# combo_-_no_usb.net
KiCad netlist of a schematic drawn in EAGLE
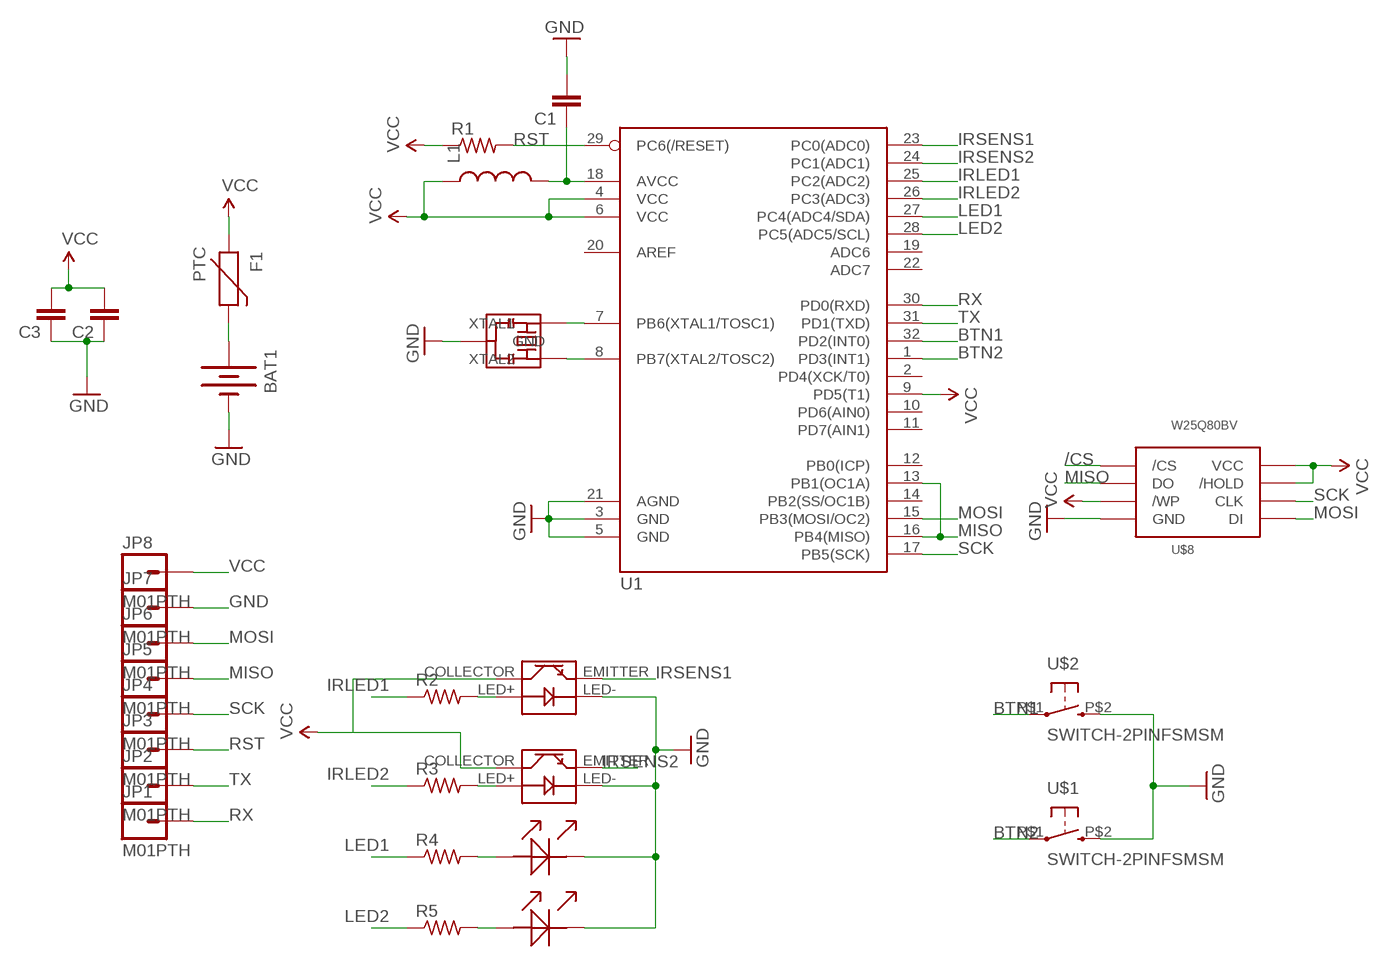
[diagram p0: schematic, sheet 1]

(export (version "E")
  (design (tool "Eeschema 10.0.6"))
  (components
    (comp (ref "BAT1")
      (value "BATTERYBA2032SM")
      (footprint "eagle-import:BA2032SM")
      (libsource (lib "eagle-import") (part "BATTERYBA2032SM"))
    )
    (comp (ref "C1")
      (value "CAP0805")
      (footprint "eagle-import:0805")
      (libsource (lib "eagle-import") (part "CAP0805"))
    )
    (comp (ref "C2")
      (value "CAP0805")
      (footprint "eagle-import:0805")
      (libsource (lib "eagle-import") (part "CAP0805"))
    )
    (comp (ref "C3")
      (value "CAP0805")
      (footprint "eagle-import:0805")
      (libsource (lib "eagle-import") (part "CAP0805"))
    )
    (comp (ref "F1")
      (value "PTC")
      (footprint "eagle-import:R0805")
      (libsource (lib "eagle-import") (part "PTC"))
    )
    (comp (ref "JP1")
      (value "M01PTH")
      (footprint "eagle-import:1X01")
      (libsource (lib "eagle-import") (part "M01PTH"))
    )
    (comp (ref "JP2")
      (value "M01PTH")
      (footprint "eagle-import:1X01")
      (libsource (lib "eagle-import") (part "M01PTH"))
    )
    (comp (ref "JP3")
      (value "M01PTH")
      (footprint "eagle-import:1X01")
      (libsource (lib "eagle-import") (part "M01PTH"))
    )
    (comp (ref "JP4")
      (value "M01PTH")
      (footprint "eagle-import:1X01")
      (libsource (lib "eagle-import") (part "M01PTH"))
    )
    (comp (ref "JP5")
      (value "M01PTH")
      (footprint "eagle-import:1X01")
      (libsource (lib "eagle-import") (part "M01PTH"))
    )
    (comp (ref "JP6")
      (value "M01PTH")
      (footprint "eagle-import:1X01")
      (libsource (lib "eagle-import") (part "M01PTH"))
    )
    (comp (ref "JP7")
      (value "M01PTH")
      (footprint "eagle-import:1X01")
      (libsource (lib "eagle-import") (part "M01PTH"))
    )
    (comp (ref "JP8")
      (value "M01PTH")
      (footprint "eagle-import:1X01")
      (libsource (lib "eagle-import") (part "M01PTH"))
    )
    (comp (ref "L1")
      (value "INDUCTOR0805")
      (footprint "eagle-import:0805")
      (libsource (lib "eagle-import") (part "INDUCTOR0805"))
    )
    (comp (ref "R1")
      (value "R-US_M0805")
      (footprint "eagle-import:M0805")
      (libsource (lib "eagle-import") (part "R-US_M0805"))
    )
    (comp (ref "R2")
      (value "R-US_M0805")
      (footprint "eagle-import:M0805")
      (libsource (lib "eagle-import") (part "R-US_M0805"))
    )
    (comp (ref "R3")
      (value "R-US_M0805")
      (footprint "eagle-import:M0805")
      (libsource (lib "eagle-import") (part "R-US_M0805"))
    )
    (comp (ref "R4")
      (value "R-US_M0805")
      (footprint "eagle-import:M0805")
      (libsource (lib "eagle-import") (part "R-US_M0805"))
    )
    (comp (ref "R5")
      (value "R-US_M0805")
      (footprint "eagle-import:M0805")
      (libsource (lib "eagle-import") (part "R-US_M0805"))
    )
    (comp (ref "U$1")
      (value "SWITCH-2PINFSMSM")
      (footprint "eagle-import:FSMSM-BUTTON")
      (libsource (lib "eagle-import") (part "SWITCH-2PINFSMSM"))
    )
    (comp (ref "U$2")
      (value "SWITCH-2PINFSMSM")
      (footprint "eagle-import:FSMSM-BUTTON")
      (libsource (lib "eagle-import") (part "SWITCH-2PINFSMSM"))
    )
    (comp (ref "U$3")
      (value "IR_SENSORQRE1113")
      (footprint "eagle-import:QRE1113")
      (libsource (lib "eagle-import") (part "IR_SENSORQRE1113"))
    )
    (comp (ref "U$4")
      (value "IR_SENSORQRE1113")
      (footprint "eagle-import:QRE1113")
      (libsource (lib "eagle-import") (part "IR_SENSORQRE1113"))
    )
    (comp (ref "U$5")
      (value "LED0603")
      (footprint "eagle-import:0603")
      (libsource (lib "eagle-import") (part "LED0603"))
    )
    (comp (ref "U$6")
      (value "LED0603")
      (footprint "eagle-import:0603")
      (libsource (lib "eagle-import") (part "LED0603"))
    )
    (comp (ref "U$7")
      (value "RESONATOR_W_CAPS")
      (footprint "eagle-import:AWSCR-CV")
      (libsource (lib "eagle-import") (part "RESONATOR_W_CAPS"))
    )
    (comp (ref "U$8")
      (value "W25Q80BVSOIC-08")
      (footprint "eagle-import:W25Q80BV-SOIC-208MIL")
      (libsource (lib "eagle-import") (part "W25Q80BVSOIC-08"))
    )
    (comp (ref "U1")
      (value "ATMEGA328_SMT")
      (footprint "eagle-import:TQFP32-08-THIN")
      (libsource (lib "eagle-import") (part "ATMEGA328_SMT"))
    )
  )
  (nets
    (net (code "1") (name "/BTN1") (class "Default")
      (node (ref "U$2") (pin "P$1") (pinfunction "1_P$1") (pintype "passive"))
      (node (ref "U1") (pin "32") (pinfunction "PD2(INT0)_32") (pintype "bidirectional"))
    )
    (net (code "2") (name "/BTN2") (class "Default")
      (node (ref "U$1") (pin "P$1") (pinfunction "1_P$1") (pintype "passive"))
      (node (ref "U1") (pin "1") (pinfunction "PD3(INT1)_1") (pintype "bidirectional"))
    )
    (net (code "3") (name "/IRLED1") (class "Default")
      (node (ref "R2") (pin "1") (pinfunction "1_1") (pintype "passive"))
      (node (ref "U1") (pin "25") (pinfunction "PC2(ADC2)_25") (pintype "bidirectional"))
    )
    (net (code "4") (name "/IRLED2") (class "Default")
      (node (ref "R3") (pin "1") (pinfunction "1_1") (pintype "passive"))
      (node (ref "U1") (pin "26") (pinfunction "PC3(ADC3)_26") (pintype "bidirectional"))
    )
    (net (code "5") (name "/IRSENS1") (class "Default")
      (node (ref "U$3") (pin "EMITTER") (pinfunction "EMITTER_EMITTER") (pintype "input"))
      (node (ref "U1") (pin "23") (pinfunction "PC0(ADC0)_23") (pintype "bidirectional"))
    )
    (net (code "6") (name "/IRSENS2") (class "Default")
      (node (ref "U$4") (pin "EMITTER") (pinfunction "EMITTER_EMITTER") (pintype "input"))
      (node (ref "U1") (pin "24") (pinfunction "PC1(ADC1)_24") (pintype "bidirectional"))
    )
    (net (code "7") (name "/LED1") (class "Default")
      (node (ref "R4") (pin "1") (pinfunction "1_1") (pintype "passive"))
      (node (ref "U1") (pin "27") (pinfunction "PC4(ADC4/SDA)_27") (pintype "bidirectional"))
    )
    (net (code "8") (name "/LED2") (class "Default")
      (node (ref "R5") (pin "1") (pinfunction "1_1") (pintype "passive"))
      (node (ref "U1") (pin "28") (pinfunction "PC5(ADC5/SCL)_28") (pintype "bidirectional"))
    )
    (net (code "9") (name "/MISO") (class "Default")
      (node (ref "JP5") (pin "1") (pinfunction "1_1") (pintype "passive"))
      (node (ref "U$8") (pin "DO") (pinfunction "DO_DO") (pintype "bidirectional"))
      (node (ref "U1") (pin "13") (pinfunction "PB1(OC1A)_13") (pintype "bidirectional"))
      (node (ref "U1") (pin "16") (pinfunction "PB4(MISO)_16") (pintype "bidirectional"))
    )
    (net (code "10") (name "/MOSI") (class "Default")
      (node (ref "JP6") (pin "1") (pinfunction "1_1") (pintype "passive"))
      (node (ref "U$8") (pin "DI") (pinfunction "DI_DI") (pintype "bidirectional"))
      (node (ref "U1") (pin "15") (pinfunction "PB3(MOSI/OC2)_15") (pintype "bidirectional"))
    )
    (net (code "11") (name "/RST") (class "Default")
      (node (ref "JP3") (pin "1") (pinfunction "1_1") (pintype "passive"))
      (node (ref "R1") (pin "2") (pinfunction "2_2") (pintype "passive"))
      (node (ref "U1") (pin "29") (pinfunction "PC6(/RESET)_29") (pintype "bidirectional"))
    )
    (net (code "12") (name "/RX") (class "Default")
      (node (ref "JP1") (pin "1") (pinfunction "1_1") (pintype "passive"))
      (node (ref "U1") (pin "30") (pinfunction "PD0(RXD)_30") (pintype "bidirectional"))
    )
    (net (code "13") (name "/SCK") (class "Default")
      (node (ref "JP4") (pin "1") (pinfunction "1_1") (pintype "passive"))
      (node (ref "U$8") (pin "CLK") (pinfunction "CLK_CLK") (pintype "input"))
      (node (ref "U1") (pin "17") (pinfunction "PB5(SCK)_17") (pintype "bidirectional"))
    )
    (net (code "14") (name "/TX") (class "Default")
      (node (ref "JP2") (pin "1") (pinfunction "1_1") (pintype "passive"))
      (node (ref "U1") (pin "31") (pinfunction "PD1(TXD)_31") (pintype "bidirectional"))
    )
    (net (code "15") (name "/{slash}CS") (class "Default")
      (node (ref "U$8") (pin "/CS") (pinfunction "/CS_/CS") (pintype "input"))
    )
    (net (code "16") (name "GND") (class "Default")
      (node (ref "BAT1") (pin "-") (pinfunction "-_-") (pintype "power_in"))
      (node (ref "C1") (pin "2") (pinfunction "2_2") (pintype "passive"))
      (node (ref "C2") (pin "1") (pinfunction "1_1") (pintype "passive"))
      (node (ref "C3") (pin "1") (pinfunction "1_1") (pintype "passive"))
      (node (ref "JP7") (pin "1") (pinfunction "1_1") (pintype "passive"))
      (node (ref "U$1") (pin "P$2") (pinfunction "3_P$2") (pintype "passive"))
      (node (ref "U$2") (pin "P$2") (pinfunction "3_P$2") (pintype "passive"))
      (node (ref "U$3") (pin "LED-") (pinfunction "LED-_LED-") (pintype "input"))
      (node (ref "U$4") (pin "LED-") (pinfunction "LED-_LED-") (pintype "input"))
      (node (ref "U$5") (pin "2") (pinfunction "-_2") (pintype "bidirectional"))
      (node (ref "U$6") (pin "2") (pinfunction "-_2") (pintype "bidirectional"))
      (node (ref "U$7") (pin "GND") (pinfunction "GND_GND") (pintype "bidirectional"))
      (node (ref "U$8") (pin "GND") (pinfunction "GND_GND") (pintype "power_in"))
      (node (ref "U1") (pin "21") (pinfunction "AGND_21") (pintype "bidirectional"))
      (node (ref "U1") (pin "3") (pinfunction "GND_3") (pintype "bidirectional"))
      (node (ref "U1") (pin "5") (pinfunction "GND_5") (pintype "bidirectional"))
    )
    (net (code "17") (name "Net-(BAT1-Pad+)") (class "Default")
      (node (ref "BAT1") (pin "+") (pinfunction "+_+") (pintype "power_in"))
      (node (ref "F1") (pin "2") (pinfunction "2_2") (pintype "bidirectional"))
    )
    (net (code "18") (name "Net-(R2-Pad2)") (class "Default")
      (node (ref "R2") (pin "2") (pinfunction "2_2") (pintype "passive"))
      (node (ref "U$3") (pin "LED+") (pinfunction "LED+_LED+") (pintype "input"))
    )
    (net (code "19") (name "Net-(R3-Pad2)") (class "Default")
      (node (ref "R3") (pin "2") (pinfunction "2_2") (pintype "passive"))
      (node (ref "U$4") (pin "LED+") (pinfunction "LED+_LED+") (pintype "input"))
    )
    (net (code "20") (name "Net-(U$5-+)") (class "Default")
      (node (ref "R4") (pin "2") (pinfunction "2_2") (pintype "passive"))
      (node (ref "U$5") (pin "1") (pinfunction "+_1") (pintype "bidirectional"))
    )
    (net (code "21") (name "Net-(U$6-+)") (class "Default")
      (node (ref "R5") (pin "2") (pinfunction "2_2") (pintype "passive"))
      (node (ref "U$6") (pin "1") (pinfunction "+_1") (pintype "bidirectional"))
    )
    (net (code "22") (name "Net-(U1-AVCC)") (class "Default")
      (node (ref "C1") (pin "1") (pinfunction "1_1") (pintype "passive"))
      (node (ref "L1") (pin "2") (pinfunction "2_2") (pintype "passive"))
      (node (ref "U1") (pin "18") (pinfunction "AVCC_18") (pintype "bidirectional"))
    )
    (net (code "23") (name "Net-(U1-PB6(XTAL1{slash}TOSC1))") (class "Default")
      (node (ref "U$7") (pin "XTAL1") (pinfunction "XTAL1_XTAL1") (pintype "bidirectional"))
      (node (ref "U1") (pin "7") (pinfunction "PB6(XTAL1/TOSC1)_7") (pintype "bidirectional"))
    )
    (net (code "24") (name "Net-(U1-PB7(XTAL2{slash}TOSC2))") (class "Default")
      (node (ref "U$7") (pin "XTAL2") (pinfunction "XTAL2_XTAL2") (pintype "bidirectional"))
      (node (ref "U1") (pin "8") (pinfunction "PB7(XTAL2/TOSC2)_8") (pintype "bidirectional"))
    )
    (net (code "25") (name "VCC") (class "Default")
      (node (ref "C2") (pin "2") (pinfunction "2_2") (pintype "passive"))
      (node (ref "C3") (pin "2") (pinfunction "2_2") (pintype "passive"))
      (node (ref "F1") (pin "1") (pinfunction "1_1") (pintype "bidirectional"))
      (node (ref "JP8") (pin "1") (pinfunction "1_1") (pintype "passive"))
      (node (ref "L1") (pin "1") (pinfunction "1_1") (pintype "passive"))
      (node (ref "R1") (pin "1") (pinfunction "1_1") (pintype "passive"))
      (node (ref "U$3") (pin "COLLECTOR") (pinfunction "COLLECTOR_COLLECTOR") (pintype "input"))
      (node (ref "U$4") (pin "COLLECTOR") (pinfunction "COLLECTOR_COLLECTOR") (pintype "input"))
      (node (ref "U$8") (pin "/HOLD") (pinfunction "/HOLD_/HOLD") (pintype "bidirectional"))
      (node (ref "U$8") (pin "/WP") (pinfunction "/WP_/WP") (pintype "bidirectional"))
      (node (ref "U$8") (pin "VCC") (pinfunction "VCC_VCC") (pintype "power_in"))
      (node (ref "U1") (pin "4") (pinfunction "VCC_4") (pintype "bidirectional"))
      (node (ref "U1") (pin "6") (pinfunction "VCC_6") (pintype "bidirectional"))
      (node (ref "U1") (pin "9") (pinfunction "PD5(T1)_9") (pintype "bidirectional"))
    )
    (net (code "26") (name "unconnected-(U1-ADC6-Pad19)") (class "Default")
      (node (ref "U1") (pin "19") (pinfunction "ADC6_19") (pintype "bidirectional"))
    )
    (net (code "27") (name "unconnected-(U1-ADC7-Pad22)") (class "Default")
      (node (ref "U1") (pin "22") (pinfunction "ADC7_22") (pintype "bidirectional"))
    )
    (net (code "28") (name "unconnected-(U1-AREF-Pad20)") (class "Default")
      (node (ref "U1") (pin "20") (pinfunction "AREF_20") (pintype "bidirectional"))
    )
    (net (code "29") (name "unconnected-(U1-PB0(ICP)-Pad12)") (class "Default")
      (node (ref "U1") (pin "12") (pinfunction "PB0(ICP)_12") (pintype "bidirectional"))
    )
    (net (code "30") (name "unconnected-(U1-PB2(SS{slash}OC1B)-Pad14)") (class "Default")
      (node (ref "U1") (pin "14") (pinfunction "PB2(SS/OC1B)_14") (pintype "bidirectional"))
    )
    (net (code "31") (name "unconnected-(U1-PD4(XCK{slash}T0)-Pad2)") (class "Default")
      (node (ref "U1") (pin "2") (pinfunction "PD4(XCK/T0)_2") (pintype "bidirectional"))
    )
    (net (code "32") (name "unconnected-(U1-PD6(AIN0)-Pad10)") (class "Default")
      (node (ref "U1") (pin "10") (pinfunction "PD6(AIN0)_10") (pintype "bidirectional"))
    )
    (net (code "33") (name "unconnected-(U1-PD7(AIN1)-Pad11)") (class "Default")
      (node (ref "U1") (pin "11") (pinfunction "PD7(AIN1)_11") (pintype "bidirectional"))
    )
  )
)
